# FIT_HDMI_X21-17.net
KiCad netlist of a schematic drawn in Altium Designer
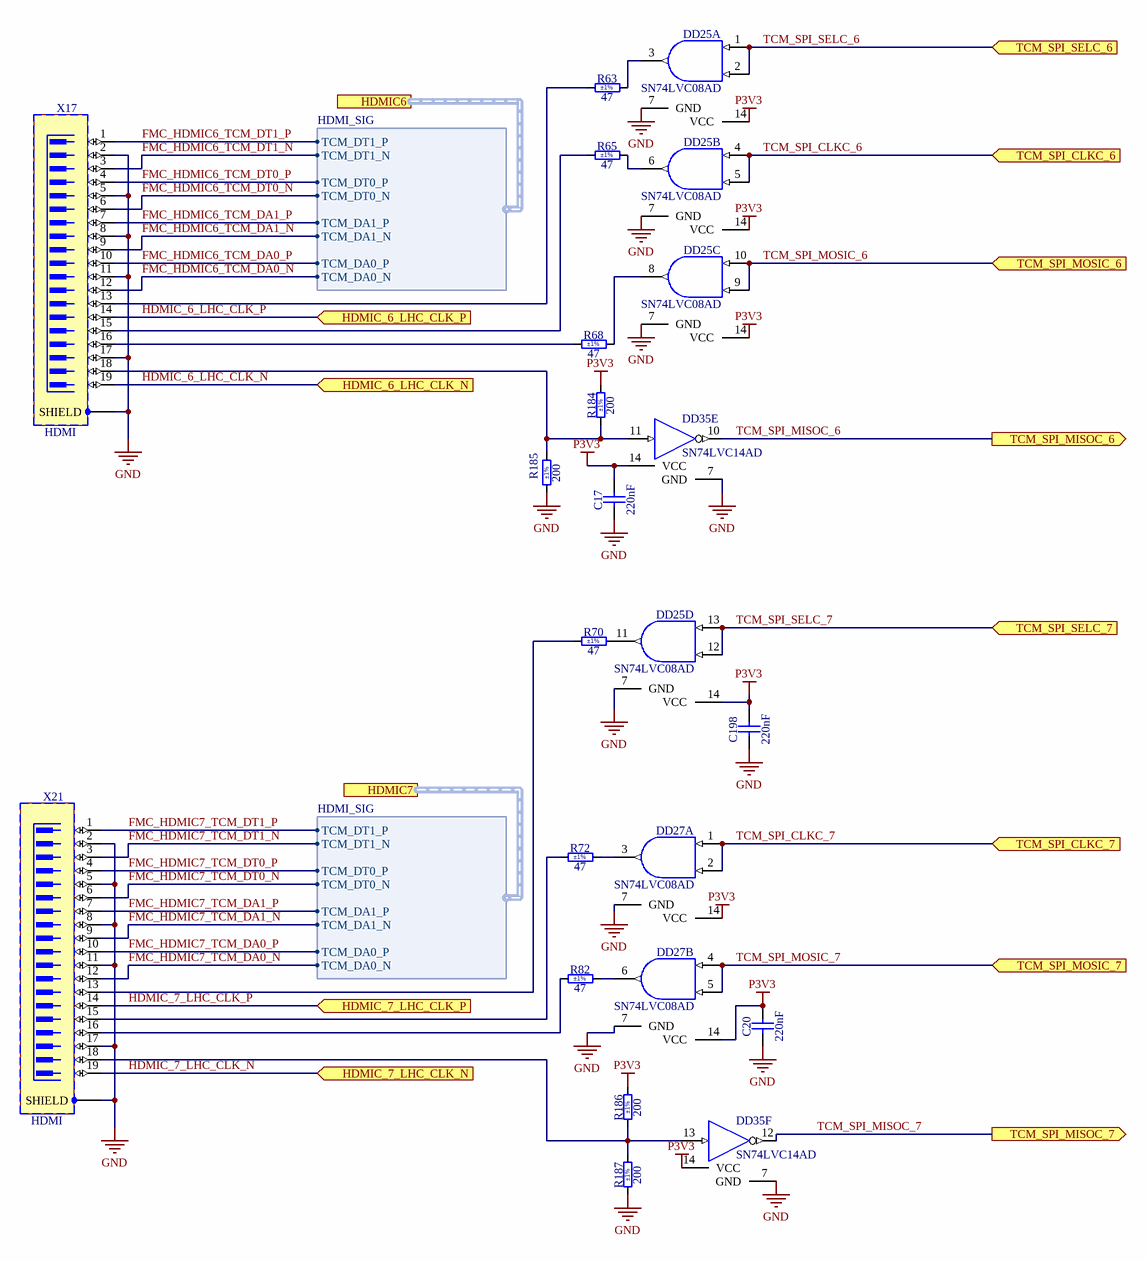
[diagram p0: FIT_HDMI_X21-17.SchDoc]

(export (version "E")
  (design (tool "Eeschema 10.0.6"))
  (components
    (comp (ref "C17")
      (value "220nF")
      (footprint "CAPC2012X135N")
      (description "Non-polarised capacitor")
      (fields
        (field (name "PART NUMBER") "CC0805_220NF_50V_10%_X7R")
        (field (name "VOLTAGE") "50V")
        (field (name "AUTHOR") "CERN DEM JLC")
      )
      (libsource (lib "Capacitors") (part "Capacitor - non polarized"))
    )
    (comp (ref "C20")
      (value "220nF")
      (footprint "CAPC2012X135N")
      (description "Non-polarised capacitor")
      (fields
        (field (name "PART NUMBER") "CC0805_220NF_50V_10%_X7R")
        (field (name "VOLTAGE") "50V")
        (field (name "AUTHOR") "CERN DEM JLC")
      )
      (libsource (lib "Capacitors") (part "Capacitor - non polarized"))
    )
    (comp (ref "C198")
      (value "220nF")
      (footprint "CAPC2012X135N")
      (description "Non-polarised capacitor")
      (fields
        (field (name "PART NUMBER") "CC0805_220NF_50V_10%_X7R")
        (field (name "VOLTAGE") "50V")
        (field (name "AUTHOR") "CERN DEM JLC")
      )
      (libsource (lib "Capacitors") (part "Capacitor - non polarized"))
    )
    (comp (ref "DD25")
      (value "SN74LVC08AD")
      (footprint "SOIC127P600X175-14N")
      (description "Quad 2-Input AND Gate")
      (fields (field (name "MANUFACTURER") "TEXAS INSTRUMENTS") (field (name "AUTHOR") "CERN DEM JLC"))
      (libsource (lib "ICs And Semiconductors") (part "7408"))
    )
    (comp (ref "DD27")
      (value "SN74LVC08AD")
      (footprint "SOIC127P600X175-14N")
      (description "Quad 2-Input AND Gate")
      (fields (field (name "MANUFACTURER") "TEXAS INSTRUMENTS") (field (name "AUTHOR") "CERN DEM JLC"))
      (libsource (lib "ICs And Semiconductors") (part "7408"))
    )
    (comp (ref "DD35")
      (value "SN74LVC14AD")
      (footprint "SOIC127P600X175-14N")
      (description "Hex Schmitt-Trigger Inverter")
      (fields (field (name "MANUFACTURER") "TEXAS INSTRUMENTS") (field (name "AUTHOR") "CERN DEM JMW"))
      (libsource (lib "ICs And Semiconductors") (part "7414"))
    )
    (comp (ref "R63")
      (value "47")
      (footprint "RESC2012X60N")
      (description "Resistor - 1%")
      (fields
        (field (name "TOLERANCE") "±1%")
        (field (name "PART NUMBER") "R0805_47R_1%_0.125W_100PPM")
        (field (name "POWER") "0.125W")
        (field (name "AUTHOR") "CERN DEM JLC")
      )
      (libsource (lib "Resistors") (part "Resistor - 1%"))
    )
    (comp (ref "R65")
      (value "47")
      (footprint "RESC2012X60N")
      (description "Resistor - 1%")
      (fields
        (field (name "TOLERANCE") "±1%")
        (field (name "PART NUMBER") "R0805_47R_1%_0.125W_100PPM")
        (field (name "POWER") "0.125W")
        (field (name "AUTHOR") "CERN DEM JLC")
      )
      (libsource (lib "Resistors") (part "Resistor - 1%"))
    )
    (comp (ref "R68")
      (value "47")
      (footprint "RESC2012X60N")
      (description "Resistor - 1%")
      (fields
        (field (name "TOLERANCE") "±1%")
        (field (name "PART NUMBER") "R0805_47R_1%_0.125W_100PPM")
        (field (name "POWER") "0.125W")
        (field (name "AUTHOR") "CERN DEM JLC")
      )
      (libsource (lib "Resistors") (part "Resistor - 1%"))
    )
    (comp (ref "R70")
      (value "47")
      (footprint "RESC2012X60N")
      (description "Resistor - 1%")
      (fields
        (field (name "TOLERANCE") "±1%")
        (field (name "PART NUMBER") "R0805_47R_1%_0.125W_100PPM")
        (field (name "POWER") "0.125W")
        (field (name "AUTHOR") "CERN DEM JLC")
      )
      (libsource (lib "Resistors") (part "Resistor - 1%"))
    )
    (comp (ref "R72")
      (value "47")
      (footprint "RESC2012X60N")
      (description "Resistor - 1%")
      (fields
        (field (name "TOLERANCE") "±1%")
        (field (name "PART NUMBER") "R0805_47R_1%_0.125W_100PPM")
        (field (name "POWER") "0.125W")
        (field (name "AUTHOR") "CERN DEM JLC")
      )
      (libsource (lib "Resistors") (part "Resistor - 1%"))
    )
    (comp (ref "R82")
      (value "47")
      (footprint "RESC2012X60N")
      (description "Resistor - 1%")
      (fields
        (field (name "TOLERANCE") "±1%")
        (field (name "PART NUMBER") "R0805_47R_1%_0.125W_100PPM")
        (field (name "POWER") "0.125W")
        (field (name "AUTHOR") "CERN DEM JLC")
      )
      (libsource (lib "Resistors") (part "Resistor - 1%"))
    )
    (comp (ref "R184")
      (value "200")
      (footprint "RESC2012X60N")
      (description "Resistor - 1%")
      (fields
        (field (name "TOLERANCE") "±1%")
        (field (name "PART NUMBER") "R0805_200R_1%_0.125W_100PPM")
        (field (name "POWER") "0.125W")
        (field (name "AUTHOR") "CERN DEM JLC")
      )
      (libsource (lib "Resistors") (part "Resistor - 1%"))
    )
    (comp (ref "R185")
      (value "200")
      (footprint "RESC2012X60N")
      (description "Resistor - 1%")
      (fields
        (field (name "TOLERANCE") "±1%")
        (field (name "PART NUMBER") "R0805_200R_1%_0.125W_100PPM")
        (field (name "POWER") "0.125W")
        (field (name "AUTHOR") "CERN DEM JLC")
      )
      (libsource (lib "Resistors") (part "Resistor - 1%"))
    )
    (comp (ref "R186")
      (value "200")
      (footprint "RESC2012X60N")
      (description "Resistor - 1%")
      (fields
        (field (name "TOLERANCE") "±1%")
        (field (name "PART NUMBER") "R0805_200R_1%_0.125W_100PPM")
        (field (name "POWER") "0.125W")
        (field (name "AUTHOR") "CERN DEM JLC")
      )
      (libsource (lib "Resistors") (part "Resistor - 1%"))
    )
    (comp (ref "R187")
      (value "200")
      (footprint "RESC2012X60N")
      (description "Resistor - 1%")
      (fields
        (field (name "TOLERANCE") "±1%")
        (field (name "PART NUMBER") "R0805_200R_1%_0.125W_100PPM")
        (field (name "POWER") "0.125W")
        (field (name "AUTHOR") "CERN DEM JLC")
      )
      (libsource (lib "Resistors") (part "Resistor - 1%"))
    )
    (comp (ref "X17")
      (value "HDMI")
      (footprint "TYCO_2007435-1")
      (description "Connector HDMI 19 Male + 1 Shield")
      (fields
        (field (name "PART NUMBER") "TYCO_2007435-1")
        (field (name "MANUFACTURER") "TYCO ELECTRONICS")
        (field (name "AUTHOR") "CERN DEM MR")
      )
      (libsource (lib "Connectors") (part "Connector HDMI 19 Male + 1 Shield"))
    )
    (comp (ref "X21")
      (value "HDMI")
      (footprint "TYCO_2007435-1")
      (description "Connector HDMI 19 Male + 1 Shield")
      (fields
        (field (name "PART NUMBER") "TYCO_2007435-1")
        (field (name "MANUFACTURER") "TYCO ELECTRONICS")
        (field (name "AUTHOR") "CERN DEM MR")
      )
      (libsource (lib "Connectors") (part "Connector HDMI 19 Male + 1 Shield"))
    )
  )
  (nets
    (net (code "2") (name "/FMC_HDMIC6_TCM_DA0_N") (class "Default")
      (node (ref "X17") (pin "12") (pinfunction "12_12") (pintype "bidirectional"))
    )
    (net (code "3") (name "/FMC_HDMIC6_TCM_DA0_P") (class "Default")
      (node (ref "X17") (pin "10") (pinfunction "10_10") (pintype "bidirectional"))
    )
    (net (code "4") (name "/FMC_HDMIC6_TCM_DA1_N") (class "Default")
      (node (ref "X17") (pin "9") (pinfunction "9_9") (pintype "bidirectional"))
    )
    (net (code "5") (name "/FMC_HDMIC6_TCM_DA1_P") (class "Default")
      (node (ref "X17") (pin "7") (pinfunction "7_7") (pintype "bidirectional"))
    )
    (net (code "6") (name "/FMC_HDMIC6_TCM_DT0_N") (class "Default")
      (node (ref "X17") (pin "6") (pinfunction "6_6") (pintype "bidirectional"))
    )
    (net (code "7") (name "/FMC_HDMIC6_TCM_DT0_P") (class "Default")
      (node (ref "X17") (pin "4") (pinfunction "4_4") (pintype "bidirectional"))
    )
    (net (code "8") (name "/FMC_HDMIC6_TCM_DT1_N") (class "Default")
      (node (ref "X17") (pin "3") (pinfunction "3_3") (pintype "bidirectional"))
    )
    (net (code "9") (name "/FMC_HDMIC6_TCM_DT1_P") (class "Default")
      (node (ref "X17") (pin "1") (pinfunction "1_1") (pintype "bidirectional"))
    )
    (net (code "10") (name "/FMC_HDMIC7_TCM_DA0_N") (class "Default")
      (node (ref "X21") (pin "12") (pinfunction "12_12") (pintype "bidirectional"))
    )
    (net (code "11") (name "/FMC_HDMIC7_TCM_DA0_P") (class "Default")
      (node (ref "X21") (pin "10") (pinfunction "10_10") (pintype "bidirectional"))
    )
    (net (code "12") (name "/FMC_HDMIC7_TCM_DA1_N") (class "Default")
      (node (ref "X21") (pin "9") (pinfunction "9_9") (pintype "bidirectional"))
    )
    (net (code "13") (name "/FMC_HDMIC7_TCM_DA1_P") (class "Default")
      (node (ref "X21") (pin "7") (pinfunction "7_7") (pintype "bidirectional"))
    )
    (net (code "14") (name "/FMC_HDMIC7_TCM_DT0_N") (class "Default")
      (node (ref "X21") (pin "6") (pinfunction "6_6") (pintype "bidirectional"))
    )
    (net (code "15") (name "/FMC_HDMIC7_TCM_DT0_P") (class "Default")
      (node (ref "X21") (pin "4") (pinfunction "4_4") (pintype "bidirectional"))
    )
    (net (code "16") (name "/FMC_HDMIC7_TCM_DT1_N") (class "Default")
      (node (ref "X21") (pin "3") (pinfunction "3_3") (pintype "bidirectional"))
    )
    (net (code "17") (name "/FMC_HDMIC7_TCM_DT1_P") (class "Default")
      (node (ref "X21") (pin "1") (pinfunction "1_1") (pintype "bidirectional"))
    )
    (net (code "18") (name "/HDMIC_6_LHC_CLK_N") (class "Default")
      (node (ref "X17") (pin "19") (pinfunction "19_19") (pintype "bidirectional"))
    )
    (net (code "19") (name "/HDMIC_6_LHC_CLK_P") (class "Default")
      (node (ref "X17") (pin "14") (pinfunction "14_14") (pintype "bidirectional"))
    )
    (net (code "20") (name "/HDMIC_7_LHC_CLK_N") (class "Default")
      (node (ref "X21") (pin "19") (pinfunction "19_19") (pintype "bidirectional"))
    )
    (net (code "21") (name "/HDMIC_7_LHC_CLK_P") (class "Default")
      (node (ref "X21") (pin "14") (pinfunction "14_14") (pintype "bidirectional"))
    )
    (net (code "22") (name "/TCM_SPI_CLKC_6") (class "Default")
      (node (ref "DD25") (pin "4") (pinfunction "A_4") (pintype "input"))
      (node (ref "DD25") (pin "5") (pinfunction "B_5") (pintype "input"))
    )
    (net (code "23") (name "/TCM_SPI_CLKC_7") (class "Default")
      (node (ref "DD27") (pin "1") (pinfunction "A_1") (pintype "input"))
      (node (ref "DD27") (pin "2") (pinfunction "B_2") (pintype "input"))
    )
    (net (code "24") (name "/TCM_SPI_MISOC_6") (class "Default")
      (node (ref "DD35") (pin "10") (pinfunction "OUT_10") (pintype "output"))
    )
    (net (code "25") (name "/TCM_SPI_MISOC_7") (class "Default")
      (node (ref "DD35") (pin "12") (pinfunction "OUT_12") (pintype "output"))
    )
    (net (code "26") (name "/TCM_SPI_MOSIC_6") (class "Default")
      (node (ref "DD25") (pin "10") (pinfunction "A_10") (pintype "input"))
      (node (ref "DD25") (pin "9") (pinfunction "B_9") (pintype "input"))
    )
    (net (code "27") (name "/TCM_SPI_MOSIC_7") (class "Default")
      (node (ref "DD27") (pin "4") (pinfunction "A_4") (pintype "input"))
      (node (ref "DD27") (pin "5") (pinfunction "B_5") (pintype "input"))
    )
    (net (code "28") (name "/TCM_SPI_SELC_6") (class "Default")
      (node (ref "DD25") (pin "1") (pinfunction "A_1") (pintype "input"))
      (node (ref "DD25") (pin "2") (pinfunction "B_2") (pintype "input"))
    )
    (net (code "29") (name "/TCM_SPI_SELC_7") (class "Default")
      (node (ref "DD25") (pin "12") (pinfunction "B_12") (pintype "input"))
      (node (ref "DD25") (pin "13") (pinfunction "A_13") (pintype "input"))
    )
    (net (code "31") (name "GND") (class "Default")
      (node (ref "C17") (pin "1") (pinfunction "1_1") (pintype "passive"))
      (node (ref "C198") (pin "1") (pinfunction "1_1") (pintype "passive"))
      (node (ref "C20") (pin "1") (pinfunction "1_1") (pintype "passive"))
      (node (ref "DD25") (pin "7") (pinfunction "GND_7") (pintype "power_in"))
      (node (ref "DD27") (pin "7") (pinfunction "GND_7") (pintype "power_in"))
      (node (ref "DD35") (pin "7") (pinfunction "GND_7") (pintype "power_in"))
      (node (ref "R185") (pin "1") (pinfunction "1_1") (pintype "passive"))
      (node (ref "R187") (pin "1") (pinfunction "1_1") (pintype "passive"))
      (node (ref "X17") (pin "11") (pinfunction "11_11") (pintype "bidirectional"))
      (node (ref "X17") (pin "17") (pinfunction "17_17") (pintype "bidirectional"))
      (node (ref "X17") (pin "2") (pinfunction "2_2") (pintype "bidirectional"))
      (node (ref "X17") (pin "5") (pinfunction "5_5") (pintype "bidirectional"))
      (node (ref "X17") (pin "8") (pinfunction "8_8") (pintype "bidirectional"))
      (node (ref "X17") (pin "SHIELD") (pinfunction "SHIELD_SHIELD") (pintype "power_in"))
      (node (ref "X21") (pin "11") (pinfunction "11_11") (pintype "bidirectional"))
      (node (ref "X21") (pin "17") (pinfunction "17_17") (pintype "bidirectional"))
      (node (ref "X21") (pin "2") (pinfunction "2_2") (pintype "bidirectional"))
      (node (ref "X21") (pin "5") (pinfunction "5_5") (pintype "bidirectional"))
      (node (ref "X21") (pin "8") (pinfunction "8_8") (pintype "bidirectional"))
      (node (ref "X21") (pin "SHIELD") (pinfunction "SHIELD_SHIELD") (pintype "power_in"))
    )
    (net (code "32") (name "Net-(DD25A-Y)") (class "Default")
      (node (ref "DD25") (pin "3") (pinfunction "Y_3") (pintype "output"))
      (node (ref "R63") (pin "2") (pinfunction "2_2") (pintype "passive"))
    )
    (net (code "33") (name "Net-(DD25B-Y)") (class "Default")
      (node (ref "DD25") (pin "6") (pinfunction "Y_6") (pintype "output"))
      (node (ref "R65") (pin "2") (pinfunction "2_2") (pintype "passive"))
    )
    (net (code "34") (name "Net-(DD25C-Y)") (class "Default")
      (node (ref "DD25") (pin "8") (pinfunction "Y_8") (pintype "output"))
      (node (ref "R68") (pin "2") (pinfunction "2_2") (pintype "passive"))
    )
    (net (code "35") (name "Net-(DD25D-Y)") (class "Default")
      (node (ref "DD25") (pin "11") (pinfunction "Y_11") (pintype "output"))
      (node (ref "R70") (pin "2") (pinfunction "2_2") (pintype "passive"))
    )
    (net (code "36") (name "Net-(DD27A-Y)") (class "Default")
      (node (ref "DD27") (pin "3") (pinfunction "Y_3") (pintype "output"))
      (node (ref "R72") (pin "2") (pinfunction "2_2") (pintype "passive"))
    )
    (net (code "37") (name "Net-(DD27B-Y)") (class "Default")
      (node (ref "DD27") (pin "6") (pinfunction "Y_6") (pintype "output"))
      (node (ref "R82") (pin "2") (pinfunction "2_2") (pintype "passive"))
    )
    (net (code "38") (name "Net-(DD35E-IN)") (class "Default")
      (node (ref "DD35") (pin "11") (pinfunction "IN_11") (pintype "input"))
      (node (ref "R184") (pin "1") (pinfunction "1_1") (pintype "passive"))
      (node (ref "R185") (pin "2") (pinfunction "2_2") (pintype "passive"))
      (node (ref "X17") (pin "18") (pinfunction "18_18") (pintype "bidirectional"))
    )
    (net (code "39") (name "Net-(DD35F-IN)") (class "Default")
      (node (ref "DD35") (pin "13") (pinfunction "IN_13") (pintype "input"))
      (node (ref "R186") (pin "1") (pinfunction "1_1") (pintype "passive"))
      (node (ref "R187") (pin "2") (pinfunction "2_2") (pintype "passive"))
      (node (ref "X21") (pin "18") (pinfunction "18_18") (pintype "bidirectional"))
    )
    (net (code "40") (name "Net-(R63-Pad1)") (class "Default")
      (node (ref "R63") (pin "1") (pinfunction "1_1") (pintype "passive"))
      (node (ref "X17") (pin "13") (pinfunction "13_13") (pintype "bidirectional"))
    )
    (net (code "41") (name "Net-(R65-Pad1)") (class "Default")
      (node (ref "R65") (pin "1") (pinfunction "1_1") (pintype "passive"))
      (node (ref "X17") (pin "15") (pinfunction "15_15") (pintype "bidirectional"))
    )
    (net (code "42") (name "Net-(R68-Pad1)") (class "Default")
      (node (ref "R68") (pin "1") (pinfunction "1_1") (pintype "passive"))
      (node (ref "X17") (pin "16") (pinfunction "16_16") (pintype "bidirectional"))
    )
    (net (code "43") (name "Net-(R70-Pad1)") (class "Default")
      (node (ref "R70") (pin "1") (pinfunction "1_1") (pintype "passive"))
      (node (ref "X21") (pin "13") (pinfunction "13_13") (pintype "bidirectional"))
    )
    (net (code "44") (name "Net-(R72-Pad1)") (class "Default")
      (node (ref "R72") (pin "1") (pinfunction "1_1") (pintype "passive"))
      (node (ref "X21") (pin "15") (pinfunction "15_15") (pintype "bidirectional"))
    )
    (net (code "45") (name "Net-(R82-Pad1)") (class "Default")
      (node (ref "R82") (pin "1") (pinfunction "1_1") (pintype "passive"))
      (node (ref "X21") (pin "16") (pinfunction "16_16") (pintype "bidirectional"))
    )
    (net (code "46") (name "P3V3") (class "Default")
      (node (ref "C17") (pin "2") (pinfunction "2_2") (pintype "passive"))
      (node (ref "C198") (pin "2") (pinfunction "2_2") (pintype "passive"))
      (node (ref "C20") (pin "2") (pinfunction "2_2") (pintype "passive"))
      (node (ref "DD25") (pin "14") (pinfunction "VCC_14") (pintype "power_in"))
      (node (ref "DD27") (pin "14") (pinfunction "VCC_14") (pintype "power_in"))
      (node (ref "DD35") (pin "14") (pinfunction "VCC_14") (pintype "power_in"))
      (node (ref "R184") (pin "2") (pinfunction "2_2") (pintype "passive"))
      (node (ref "R186") (pin "2") (pinfunction "2_2") (pintype "passive"))
    )
  )
)
